# HAE_HMI.net
KiCad netlist of a schematic drawn in Altium Designer
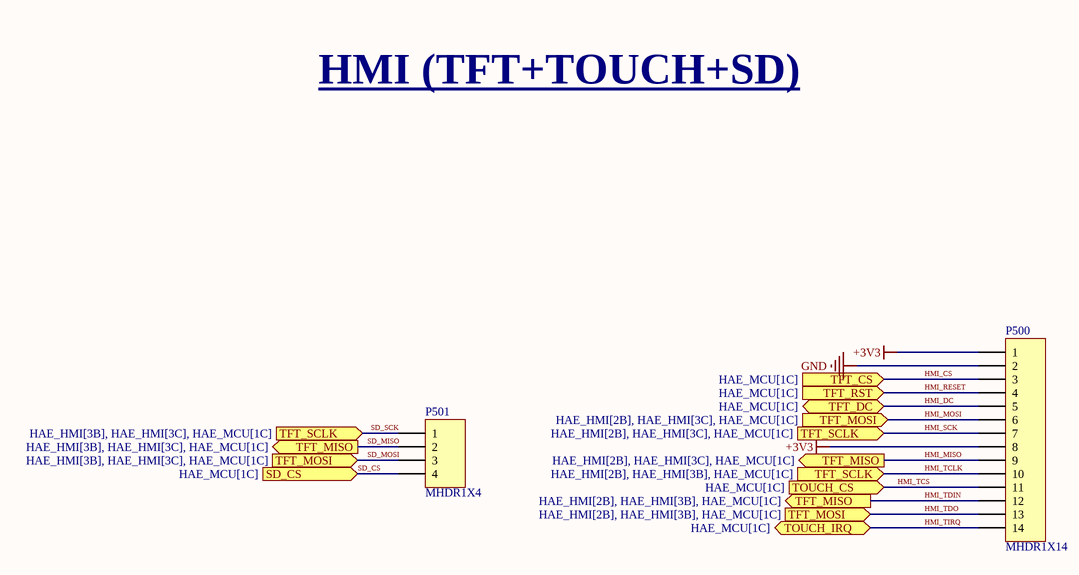
[diagram p0: HAE_HMI.SchDoc]

(export (version "E")
  (design (tool "Eeschema 10.0.6"))
  (components
    (comp (ref "P500")
      (value "MHDR1X14")
      (footprint "MHDR1X14")
      (description "Header, 14-Pin")
      (fields (field (name "PUBLISHER") "Altium Limited"))
      (libsource (lib "Miscellaneous+Connectors") (part "MHDR1X14"))
    )
    (comp (ref "P501")
      (value "MHDR1X4")
      (footprint "MHDR1X4")
      (description "Header, 4-Pin")
      (fields (field (name "PUBLISHER") "Altium Limited"))
      (libsource (lib "Miscellaneous+Connectors") (part "MHDR1X4"))
    )
  )
  (nets
    (net (code "1") (name "+3V3") (class "Default")
      (node (ref "P500") (pin "1") (pinfunction "1_1") (pintype "passive"))
      (node (ref "P500") (pin "8") (pinfunction "8_8") (pintype "passive"))
    )
    (net (code "2") (name "/HMI_CS") (class "Default")
      (node (ref "P500") (pin "3") (pinfunction "3_3") (pintype "passive"))
    )
    (net (code "3") (name "/HMI_DC") (class "Default")
      (node (ref "P500") (pin "5") (pinfunction "5_5") (pintype "passive"))
    )
    (net (code "4") (name "/HMI_MISO") (class "Default")
      (node (ref "P500") (pin "12") (pinfunction "12_12") (pintype "passive"))
      (node (ref "P500") (pin "9") (pinfunction "9_9") (pintype "passive"))
      (node (ref "P501") (pin "2") (pinfunction "2_2") (pintype "passive"))
    )
    (net (code "5") (name "/HMI_MOSI") (class "Default")
      (node (ref "P500") (pin "13") (pinfunction "13_13") (pintype "passive"))
      (node (ref "P500") (pin "6") (pinfunction "6_6") (pintype "passive"))
      (node (ref "P501") (pin "3") (pinfunction "3_3") (pintype "passive"))
    )
    (net (code "6") (name "/HMI_RESET") (class "Default")
      (node (ref "P500") (pin "4") (pinfunction "4_4") (pintype "passive"))
    )
    (net (code "7") (name "/HMI_SCK") (class "Default")
      (node (ref "P500") (pin "10") (pinfunction "10_10") (pintype "passive"))
      (node (ref "P500") (pin "7") (pinfunction "7_7") (pintype "passive"))
      (node (ref "P501") (pin "1") (pinfunction "1_1") (pintype "passive"))
    )
    (net (code "8") (name "/HMI_TCS") (class "Default")
      (node (ref "P500") (pin "11") (pinfunction "11_11") (pintype "passive"))
    )
    (net (code "9") (name "/HMI_TIRQ") (class "Default")
      (node (ref "P500") (pin "14") (pinfunction "14_14") (pintype "passive"))
    )
    (net (code "10") (name "/SD_CS") (class "Default")
      (node (ref "P501") (pin "4") (pinfunction "4_4") (pintype "passive"))
    )
    (net (code "11") (name "GND") (class "Default")
      (node (ref "P500") (pin "2") (pinfunction "2_2") (pintype "passive"))
    )
  )
)
